# Sheet1.net
KiCad netlist of a schematic drawn in Altium Designer
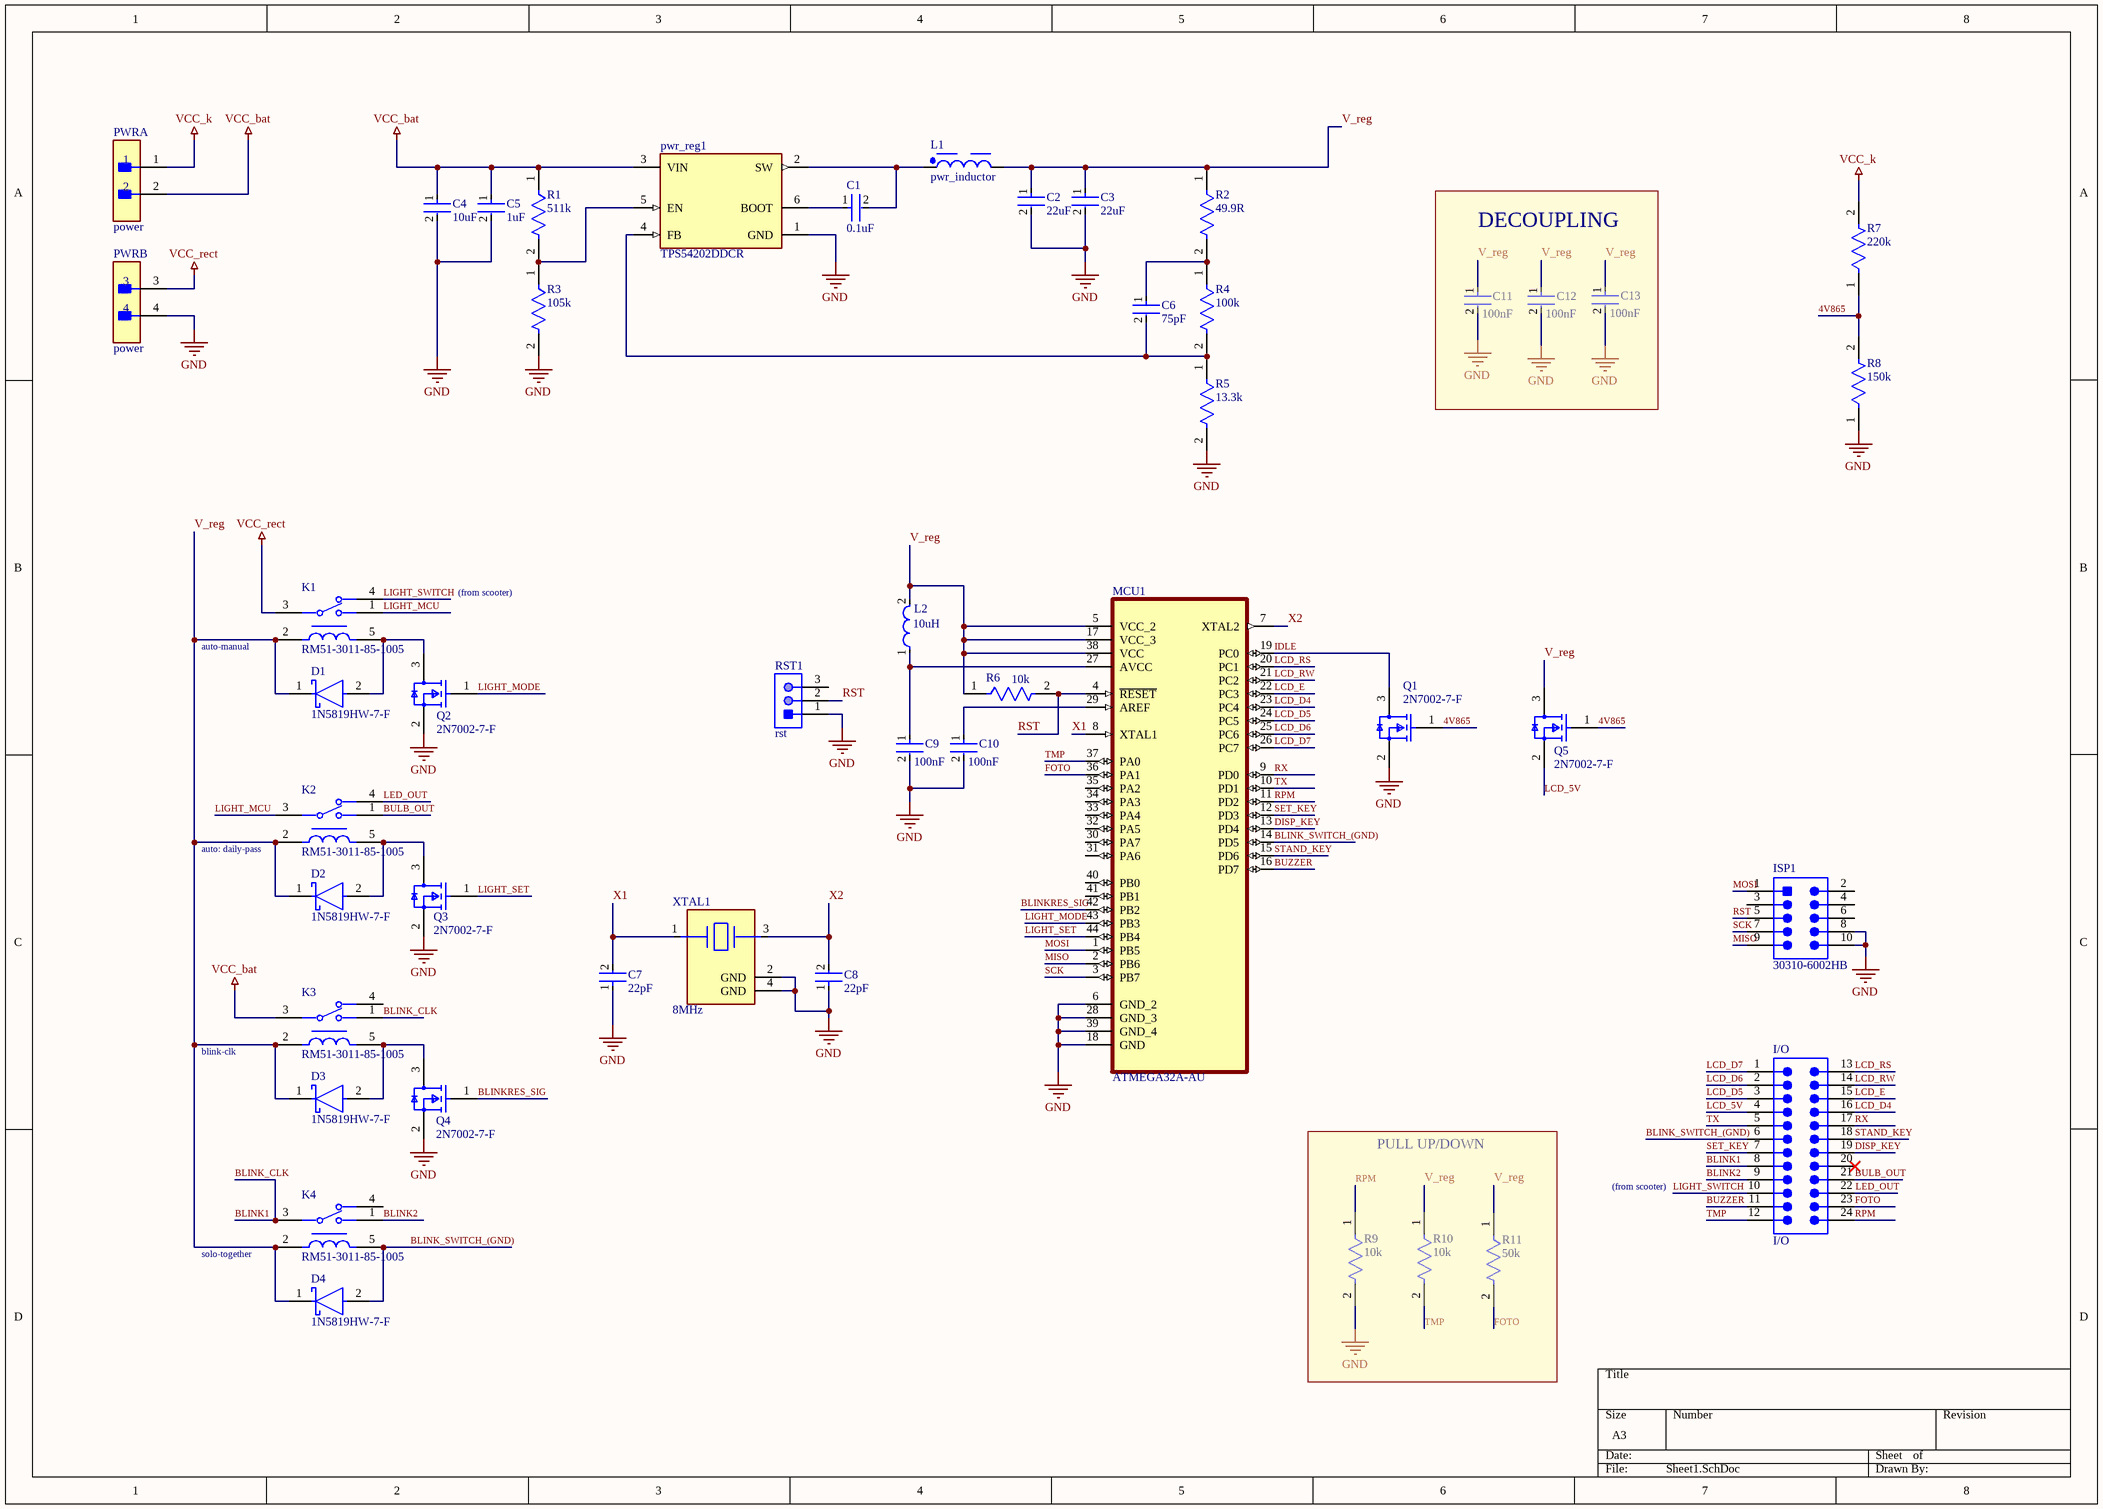
[diagram p0: Sheet1.SchDoc]

(export (version "E")
  (design (tool "Eeschema 10.0.6"))
  (components
    (comp (ref "C1")
      (value "0.1uF")
      (footprint "FP-CL10-IPC_A")
      (description "Cap Ceramic 0.1uF 25V SMD 0603")
      (fields (field (name "VOLTAGE") "50V") (field (name "TOLERANCE") "10%"))
      (libsource (lib "Altium Content Vault") (part "b4654b650e69147ec39a6b967a45e02"))
    )
    (comp (ref "C2")
      (value "22uF")
      (footprint "FP-CL10-IPC_A")
      (description "Cap Ceramic 22uF 25V X7R LOW ESR SMD 0603")
      (fields (field (name "VOLTAGE") "50V") (field (name "TOLERANCE") "10%"))
      (libsource (lib "Altium Content Vault") (part "b4654b650e69147ec39a6b967a45e02"))
    )
    (comp (ref "C3")
      (value "22uF")
      (footprint "FP-CL10-IPC_A")
      (description "Cap Ceramic 22uF 25V X7R LOW ESR SMD 0603")
      (fields (field (name "VOLTAGE") "50V") (field (name "TOLERANCE") "10%"))
      (libsource (lib "Altium Content Vault") (part "b4654b650e69147ec39a6b967a45e02"))
    )
    (comp (ref "C4")
      (value "10uF")
      (footprint "FP-CL10-IPC_A")
      (description "Cap Ceramic 10uF 25V SMD 0603")
      (fields (field (name "VOLTAGE") "50V") (field (name "TOLERANCE") "10%"))
      (libsource (lib "Altium Content Vault") (part "b4654b650e69147ec39a6b967a45e02"))
    )
    (comp (ref "C5")
      (value "1uF")
      (footprint "FP-CL10-IPC_A")
      (description "Cap Ceramic 1uF 25V SMD 0603")
      (fields (field (name "VOLTAGE") "50V") (field (name "TOLERANCE") "10%"))
      (libsource (lib "Altium Content Vault") (part "b4654b650e69147ec39a6b967a45e02"))
    )
    (comp (ref "C6")
      (value "75pF")
      (footprint "FP-CL10-IPC_A")
      (description "Cap Ceramic 75pF 25V SMD 0603")
      (fields (field (name "VOLTAGE") "50V") (field (name "TOLERANCE") "10%"))
      (libsource (lib "Altium Content Vault") (part "b4654b650e69147ec39a6b967a45e02"))
    )
    (comp (ref "C7")
      (value "22pF")
      (footprint "FP-CL10-IPC_A")
      (description "Cap Ceramic 22pF 25V SMD 0603")
      (fields (field (name "VOLTAGE") "50V") (field (name "TOLERANCE") "10%"))
      (libsource (lib "Altium Content Vault") (part "b4654b650e69147ec39a6b967a45e02"))
    )
    (comp (ref "C8")
      (value "22pF")
      (footprint "FP-CL10-IPC_A")
      (description "Cap Ceramic 22pF 25V SMD 0603")
      (fields (field (name "VOLTAGE") "50V") (field (name "TOLERANCE") "10%"))
      (libsource (lib "Altium Content Vault") (part "b4654b650e69147ec39a6b967a45e02"))
    )
    (comp (ref "C9")
      (value "100nF")
      (footprint "FP-CL10-IPC_A")
      (description "Cap Ceramic 100nF 50V X7R ±10% Pad SMD 0603 +125°C T/R")
      (fields (field (name "VOLTAGE") "50V") (field (name "TOLERANCE") "10%"))
      (libsource (lib "Altium Content Vault") (part "b4654b650e69147ec39a6b967a45e02"))
    )
    (comp (ref "C10")
      (value "100nF")
      (footprint "FP-CL10-IPC_A")
      (description "Cap Ceramic 100nF 50V X7R ±10% Pad SMD 0603 +125°C T/R")
      (fields (field (name "VOLTAGE") "50V") (field (name "TOLERANCE") "10%"))
      (libsource (lib "Altium Content Vault") (part "b4654b650e69147ec39a6b967a45e02"))
    )
    (comp (ref "C11")
      (value "100nF")
      (footprint "FP-CL10-IPC_A")
      (description "Cap Ceramic 100nF 50V X7R ±10% Pad SMD 0603 +125°C T/R")
      (fields (field (name "VOLTAGE") "50V") (field (name "TOLERANCE") "10%"))
      (libsource (lib "Altium Content Vault") (part "b4654b650e69147ec39a6b967a45e02"))
    )
    (comp (ref "C12")
      (value "100nF")
      (footprint "FP-CL10-IPC_A")
      (description "Cap Ceramic 100nF 50V X7R ±10% Pad SMD 0603 +125°C T/R")
      (fields (field (name "VOLTAGE") "50V") (field (name "TOLERANCE") "10%"))
      (libsource (lib "Altium Content Vault") (part "b4654b650e69147ec39a6b967a45e02"))
    )
    (comp (ref "C13")
      (value "100nF")
      (footprint "FP-CL10-IPC_A")
      (description "Cap Ceramic 100nF 50V X7R ±10% Pad SMD 0603 +125°C T/R")
      (fields (field (name "VOLTAGE") "50V") (field (name "TOLERANCE") "10%"))
      (libsource (lib "Altium Content Vault") (part "b4654b650e69147ec39a6b967a45e02"))
    )
    (comp (ref "D1")
      (value "1N5819HW-7-F")
      (footprint "FP-SOD123-IPC_A")
      (description "DIODE SCHOTTKY 40V 1A SOD123")
      (libsource (lib "Altium Content Vault") (part "1d6ec82d83fb6aee721767c19dac4b9"))
    )
    (comp (ref "D2")
      (value "1N5819HW-7-F")
      (footprint "FP-SOD123-IPC_A")
      (description "DIODE SCHOTTKY 40V 1A SOD123")
      (libsource (lib "Altium Content Vault") (part "1d6ec82d83fb6aee721767c19dac4b9"))
    )
    (comp (ref "D3")
      (value "1N5819HW-7-F")
      (footprint "FP-SOD123-IPC_A")
      (description "DIODE SCHOTTKY 40V 1A SOD123")
      (libsource (lib "Altium Content Vault") (part "1d6ec82d83fb6aee721767c19dac4b9"))
    )
    (comp (ref "D4")
      (value "1N5819HW-7-F")
      (footprint "FP-SOD123-IPC_A")
      (description "DIODE SCHOTTKY 40V 1A SOD123")
      (libsource (lib "Altium Content Vault") (part "1d6ec82d83fb6aee721767c19dac4b9"))
    )
    (comp (ref "I/O")
      (value "I/O")
      (footprint "649024227222")
      (libsource (lib "Altium Content Vault") (part "Header_Male_2R_24P(A)"))
    )
    (comp (ref "ISP1")
      (value "30310-6002HB")
      (footprint "3M-30310-6002HB-10_V")
      (fields (field (name "MANUFACTURER") "3M"))
      (libsource (lib "Altium Content Vault") (part "CN-2P-M-R10"))
    )
    (comp (ref "K1")
      (value "RM51-3011-85-1005")
      (footprint "FP-1-1721150-0-MFG")
      (description "Relpol\r\nRM51-3011-85-1005\r\nRELAY 10A 5V")
      (fields
        (field (name "MANUFACTURER") "TE")
        (field (name "OCTOPART") "https://octopart.com/1-1721150-0-te+connectivity-41294869")
      )
      (libsource (lib "Altium Content Vault") (part "6d7f6cec76f9d90da65a396cf24d809"))
    )
    (comp (ref "K2")
      (value "RM51-3011-85-1005")
      (footprint "FP-1-1721150-0-MFG")
      (description "Relpol\r\nRM51-3011-85-1005\r\nRELAY 10A 5V")
      (fields
        (field (name "MANUFACTURER") "TE")
        (field (name "OCTOPART") "https://octopart.com/1-1721150-0-te+connectivity-41294869")
      )
      (libsource (lib "Altium Content Vault") (part "6d7f6cec76f9d90da65a396cf24d809"))
    )
    (comp (ref "K3")
      (value "RM51-3011-85-1005")
      (footprint "FP-1-1721150-0-MFG")
      (description "Relpol\r\nRM51-3011-85-1005\r\nRELAY 10A 5V")
      (fields
        (field (name "MANUFACTURER") "TE")
        (field (name "OCTOPART") "https://octopart.com/1-1721150-0-te+connectivity-41294869")
      )
      (libsource (lib "Altium Content Vault") (part "6d7f6cec76f9d90da65a396cf24d809"))
    )
    (comp (ref "K4")
      (value "RM51-3011-85-1005")
      (footprint "FP-1-1721150-0-MFG")
      (description "Relpol\r\nRM51-3011-85-1005\r\nRELAY 10A 5V")
      (fields
        (field (name "MANUFACTURER") "TE")
        (field (name "OCTOPART") "https://octopart.com/1-1721150-0-te+connectivity-41294869")
      )
      (libsource (lib "Altium Content Vault") (part "6d7f6cec76f9d90da65a396cf24d809"))
    )
    (comp (ref "L1")
      (value "pwr_inductor")
      (footprint "WE-PD_7345")
      (description "15uF, 2.7A  HPI0630-150")
      (fields (field (name "TOLERANCE") "20%"))
      (libsource (lib "Altium Content Vault") (part "Inductor - 2"))
    )
    (comp (ref "L2")
      (value "10uH")
      (footprint "FP-CBMF1608-IPC_A")
      (description "SMD Inductors 10uH ±10% 0.38A 0.468Ω 0603")
      (fields (field (name "TOLERANCE") "10%"))
      (libsource (lib "Altium Content Vault") (part "725321dda6339637d4d059423bc1c3c"))
    )
    (comp (ref "MCU1")
      (value "ATMEGA32A-AU")
      (footprint "QFP80P1200X1200X120-44N")
      (description "AVR AVRÂ® ATmega Microcontroller IC 8-Bit 16MHz 32KB (16K x 16) FLASH 44-TQFP (10x10)")
      (fields (field (name "MF") "Microchip"))
      (libsource (lib "ATMEGA32A-AU") (part "ATMEGA32A-AU"))
    )
    (comp (ref "PWR")
      (value "power")
      (footprint "FP-1586042-4-MFG")
      (description "CONN HEADER R/A 4POS 4.2MM")
      (libsource (lib "Altium Content Vault") (part "54be066d535c0aa4221644b3767ed93"))
    )
    (comp (ref "pwr_reg1")
      (value "TPS54202DDCR")
      (footprint "FP-DDC0006A-IPC_B")
      (description "IC REG BUCK ADJ 2A TSOT23-6")
      (libsource (lib "Altium Content Vault") (part "35c2d3f1afc239a386b2ba50eead654"))
    )
    (comp (ref "Q1")
      (value "2N7002-7-F")
      (footprint "FP-SOT23-MFG")
      (description "MOSFET N-CH 60V 115MA SOT23-3")
      (fields (field (name "VOLTAGE") "60V"))
      (libsource (lib "Altium Content Vault") (part "3b9c635fedb024a5347a57b145af9cc"))
    )
    (comp (ref "Q2")
      (value "2N7002-7-F")
      (footprint "FP-SOT23-MFG")
      (description "MOSFET N-CH 60V 115MA SOT23-3")
      (fields (field (name "VOLTAGE") "60V"))
      (libsource (lib "Altium Content Vault") (part "3b9c635fedb024a5347a57b145af9cc"))
    )
    (comp (ref "Q3")
      (value "2N7002-7-F")
      (footprint "FP-SOT23-MFG")
      (description "MOSFET N-CH 60V 115MA SOT23-3")
      (fields (field (name "VOLTAGE") "60V"))
      (libsource (lib "Altium Content Vault") (part "3b9c635fedb024a5347a57b145af9cc"))
    )
    (comp (ref "Q4")
      (value "2N7002-7-F")
      (footprint "FP-SOT23-MFG")
      (description "MOSFET N-CH 60V 115MA SOT23-3")
      (fields (field (name "VOLTAGE") "60V"))
      (libsource (lib "Altium Content Vault") (part "3b9c635fedb024a5347a57b145af9cc"))
    )
    (comp (ref "Q5")
      (value "2N7002-7-F")
      (footprint "FP-SOT23-MFG")
      (description "MOSFET N-CH 60V 115MA SOT23-3")
      (fields (field (name "VOLTAGE") "60V"))
      (libsource (lib "Altium Content Vault") (part "3b9c635fedb024a5347a57b145af9cc"))
    )
    (comp (ref "R1")
      (value "511k")
      (footprint "FP-CRCW0603-e3-IPC_A")
      (description "511kΩ, 0.1W, 0603")
      (fields (field (name "TOLERANCE") "1%"))
      (libsource (lib "Altium Content Vault") (part "1029c3af85768c4190bb7ad29bc67b5"))
    )
    (comp (ref "R2")
      (value "49.9R")
      (footprint "FP-CRCW0603-e3-IPC_A")
      (description "49.9Ω, 0.1W, 0603")
      (fields (field (name "TOLERANCE") "1%"))
      (libsource (lib "Altium Content Vault") (part "1029c3af85768c4190bb7ad29bc67b5"))
    )
    (comp (ref "R3")
      (value "105k")
      (footprint "FP-CRCW0603-e3-IPC_A")
      (description "105kΩ, 0.1W, 0603")
      (fields (field (name "TOLERANCE") "1%"))
      (libsource (lib "Altium Content Vault") (part "1029c3af85768c4190bb7ad29bc67b5"))
    )
    (comp (ref "R4")
      (value "100k")
      (footprint "FP-CRCW0603-e3-IPC_A")
      (description "100kΩ, 0.1W, 0603")
      (fields (field (name "TOLERANCE") "1%"))
      (libsource (lib "Altium Content Vault") (part "1029c3af85768c4190bb7ad29bc67b5"))
    )
    (comp (ref "R5")
      (value "13.3k")
      (footprint "FP-CRCW0603-e3-IPC_A")
      (description "13.3kΩ, 0.1W, 0603")
      (fields (field (name "TOLERANCE") "1%"))
      (libsource (lib "Altium Content Vault") (part "1029c3af85768c4190bb7ad29bc67b5"))
    )
    (comp (ref "R6")
      (value "10k")
      (footprint "FP-CRCW0603-e3-IPC_A")
      (description "10kΩ, 0.1W, 0603")
      (fields (field (name "TOLERANCE") "1%"))
      (libsource (lib "Altium Content Vault") (part "1029c3af85768c4190bb7ad29bc67b5"))
    )
    (comp (ref "R7")
      (value "220k")
      (footprint "FP-CRCW0603-e3-IPC_A")
      (description "220kΩ, 0.1W, 0603")
      (fields (field (name "TOLERANCE") "1%"))
      (libsource (lib "Altium Content Vault") (part "1029c3af85768c4190bb7ad29bc67b5"))
    )
    (comp (ref "R8")
      (value "150k")
      (footprint "FP-CRCW0603-e3-IPC_A")
      (description "150kΩ, 0.1W, 0603")
      (fields (field (name "TOLERANCE") "1%"))
      (libsource (lib "Altium Content Vault") (part "1029c3af85768c4190bb7ad29bc67b5"))
    )
    (comp (ref "R9")
      (value "10k")
      (footprint "FP-CRCW0603-e3-IPC_A")
      (description "10kΩ, 0.1W, 0603")
      (fields (field (name "TOLERANCE") "1%"))
      (libsource (lib "Altium Content Vault") (part "1029c3af85768c4190bb7ad29bc67b5"))
    )
    (comp (ref "R10")
      (value "10k")
      (footprint "FP-CRCW0603-e3-IPC_A")
      (description "10kΩ, 0.1W, 0603")
      (fields (field (name "TOLERANCE") "1%"))
      (libsource (lib "Altium Content Vault") (part "1029c3af85768c4190bb7ad29bc67b5"))
    )
    (comp (ref "R11")
      (value "50k")
      (footprint "FP-CRCW0603-e3-IPC_A")
      (description "50kΩ, 0.1W, 0603")
      (fields (field (name "TOLERANCE") "1%"))
      (libsource (lib "Altium Content Vault") (part "1029c3af85768c4190bb7ad29bc67b5"))
    )
    (comp (ref "RST1")
      (value "rst")
      (footprint "MOLX-22-28-4033_V")
      (description "Male Header, Pitch 2.54 mm, 1 x 3 Position, Height 8.38 mm, Tail Length 3.18 mm, RoHS, Bulk")
      (fields (field (name "MANUFACTURER") "Molex"))
      (libsource (lib "Altium Content Vault") (part "CN-1P-M-R3"))
    )
    (comp (ref "XTAL1")
      (value "8MHz")
      (footprint "FP-LFXTAL055663REEL-MFG")
      (description "LFXTAL055663REEL\r\nCRYSTAL 8.0000MHZ 18PF SMD")
      (libsource (lib "Altium Content Vault") (part "b89083c918a6a788f8f4b4140568890"))
    )
  )
  (nets
    (net (code "1") (name "/4V865") (class "Default")
      (node (ref "Q1") (pin "1") (pinfunction "G_1") (pintype "passive"))
      (node (ref "Q5") (pin "1") (pinfunction "G_1") (pintype "passive"))
      (node (ref "R7") (pin "1") (pinfunction "1_1") (pintype "passive"))
      (node (ref "R8") (pin "2") (pinfunction "2_2") (pintype "passive"))
    )
    (net (code "3") (name "/BLINK1") (class "Default")
      (node (ref "I/O") (pin "8") (pinfunction "8_8") (pintype "passive"))
      (node (ref "K3") (pin "1") (pinfunction "1_1") (pintype "passive"))
      (node (ref "K4") (pin "3") (pinfunction "3_3") (pintype "passive"))
    )
    (net (code "4") (name "/BLINK2") (class "Default")
      (node (ref "I/O") (pin "9") (pinfunction "9_9") (pintype "passive"))
      (node (ref "K4") (pin "1") (pinfunction "1_1") (pintype "passive"))
    )
    (net (code "5") (name "/BLINKRES_SIG") (class "Default")
      (node (ref "MCU1") (pin "42") (pinfunction "PB2_42") (pintype "bidirectional"))
      (node (ref "Q4") (pin "1") (pinfunction "G_1") (pintype "passive"))
    )
    (net (code "6") (name "/BLINK_SWITCH_(GND)") (class "Default")
      (node (ref "D4") (pin "2") (pinfunction "A_2") (pintype "passive"))
      (node (ref "I/O") (pin "6") (pinfunction "6_6") (pintype "passive"))
      (node (ref "K4") (pin "5") (pinfunction "5_5") (pintype "passive"))
      (node (ref "MCU1") (pin "14") (pinfunction "PD5_14") (pintype "bidirectional"))
    )
    (net (code "7") (name "/BULB_OUT") (class "Default")
      (node (ref "I/O") (pin "21") (pinfunction "21_21") (pintype "passive"))
      (node (ref "K2") (pin "1") (pinfunction "1_1") (pintype "passive"))
    )
    (net (code "8") (name "/BUZZER") (class "Default")
      (node (ref "I/O") (pin "11") (pinfunction "11_11") (pintype "passive"))
      (node (ref "MCU1") (pin "16") (pinfunction "PD7_16") (pintype "bidirectional"))
    )
    (net (code "9") (name "/DISP_KEY") (class "Default")
      (node (ref "I/O") (pin "19") (pinfunction "19_19") (pintype "passive"))
      (node (ref "MCU1") (pin "13") (pinfunction "PD4_13") (pintype "bidirectional"))
    )
    (net (code "10") (name "/FOTO") (class "Default")
      (node (ref "I/O") (pin "23") (pinfunction "23_23") (pintype "passive"))
      (node (ref "MCU1") (pin "36") (pinfunction "PA1_36") (pintype "bidirectional"))
      (node (ref "R11") (pin "2") (pinfunction "2_2") (pintype "passive"))
    )
    (net (code "11") (name "/IDLE") (class "Default")
      (node (ref "MCU1") (pin "19") (pinfunction "PC0_19") (pintype "bidirectional"))
      (node (ref "Q1") (pin "3") (pinfunction "D_3") (pintype "passive"))
    )
    (net (code "12") (name "/LCD_5V") (class "Default")
      (node (ref "I/O") (pin "4") (pinfunction "4_4") (pintype "passive"))
      (node (ref "Q5") (pin "2") (pinfunction "S_2") (pintype "passive"))
    )
    (net (code "13") (name "/LCD_D4") (class "Default")
      (node (ref "I/O") (pin "16") (pinfunction "16_16") (pintype "passive"))
      (node (ref "MCU1") (pin "23") (pinfunction "PC4_23") (pintype "bidirectional"))
    )
    (net (code "14") (name "/LCD_D5") (class "Default")
      (node (ref "I/O") (pin "3") (pinfunction "3_3") (pintype "passive"))
      (node (ref "MCU1") (pin "24") (pinfunction "PC5_24") (pintype "bidirectional"))
    )
    (net (code "15") (name "/LCD_D6") (class "Default")
      (node (ref "I/O") (pin "2") (pinfunction "2_2") (pintype "passive"))
      (node (ref "MCU1") (pin "25") (pinfunction "PC6_25") (pintype "bidirectional"))
    )
    (net (code "16") (name "/LCD_D7") (class "Default")
      (node (ref "I/O") (pin "1") (pinfunction "1_1") (pintype "passive"))
      (node (ref "MCU1") (pin "26") (pinfunction "PC7_26") (pintype "bidirectional"))
    )
    (net (code "17") (name "/LCD_E") (class "Default")
      (node (ref "I/O") (pin "15") (pinfunction "15_15") (pintype "passive"))
      (node (ref "MCU1") (pin "22") (pinfunction "PC3_22") (pintype "bidirectional"))
    )
    (net (code "18") (name "/LCD_RS") (class "Default")
      (node (ref "I/O") (pin "13") (pinfunction "13_13") (pintype "passive"))
      (node (ref "MCU1") (pin "20") (pinfunction "PC1_20") (pintype "bidirectional"))
    )
    (net (code "19") (name "/LCD_RW") (class "Default")
      (node (ref "I/O") (pin "14") (pinfunction "14_14") (pintype "passive"))
      (node (ref "MCU1") (pin "21") (pinfunction "PC2_21") (pintype "bidirectional"))
    )
    (net (code "20") (name "/LED_OUT") (class "Default")
      (node (ref "I/O") (pin "22") (pinfunction "22_22") (pintype "passive"))
      (node (ref "K2") (pin "4") (pinfunction "4_4") (pintype "passive"))
    )
    (net (code "21") (name "/LIGHT_MCU") (class "Default")
      (node (ref "K1") (pin "1") (pinfunction "1_1") (pintype "passive"))
      (node (ref "K2") (pin "3") (pinfunction "3_3") (pintype "passive"))
    )
    (net (code "22") (name "/LIGHT_MODE") (class "Default")
      (node (ref "MCU1") (pin "43") (pinfunction "PB3_43") (pintype "bidirectional"))
      (node (ref "Q2") (pin "1") (pinfunction "G_1") (pintype "passive"))
    )
    (net (code "23") (name "/LIGHT_SET") (class "Default")
      (node (ref "MCU1") (pin "44") (pinfunction "PB4_44") (pintype "bidirectional"))
      (node (ref "Q3") (pin "1") (pinfunction "G_1") (pintype "passive"))
    )
    (net (code "24") (name "/LIGHT_SWITCH") (class "Default")
      (node (ref "I/O") (pin "10") (pinfunction "10_10") (pintype "passive"))
      (node (ref "K1") (pin "4") (pinfunction "4_4") (pintype "passive"))
    )
    (net (code "25") (name "/MISO") (class "Default")
      (node (ref "ISP1") (pin "9") (pinfunction "9_9") (pintype "passive"))
      (node (ref "MCU1") (pin "2") (pinfunction "PB6_2") (pintype "bidirectional"))
    )
    (net (code "26") (name "/MOSI") (class "Default")
      (node (ref "ISP1") (pin "1") (pinfunction "1_1") (pintype "passive"))
      (node (ref "MCU1") (pin "1") (pinfunction "PB5_1") (pintype "bidirectional"))
    )
    (net (code "27") (name "/RPM") (class "Default")
      (node (ref "I/O") (pin "24") (pinfunction "24_24") (pintype "passive"))
      (node (ref "MCU1") (pin "11") (pinfunction "PD2_11") (pintype "bidirectional"))
      (node (ref "R9") (pin "1") (pinfunction "1_1") (pintype "passive"))
    )
    (net (code "28") (name "/RST") (class "Default")
      (node (ref "ISP1") (pin "5") (pinfunction "5_5") (pintype "passive"))
      (node (ref "MCU1") (pin "4") (pinfunction "~{RESET}_4") (pintype "input"))
      (node (ref "R6") (pin "2") (pinfunction "2_2") (pintype "passive"))
      (node (ref "RST1") (pin "2") (pinfunction "2_2") (pintype "passive"))
    )
    (net (code "29") (name "/RX") (class "Default")
      (node (ref "I/O") (pin "17") (pinfunction "17_17") (pintype "passive"))
      (node (ref "MCU1") (pin "9") (pinfunction "PD0_9") (pintype "bidirectional"))
    )
    (net (code "30") (name "/SCK") (class "Default")
      (node (ref "ISP1") (pin "7") (pinfunction "7_7") (pintype "passive"))
      (node (ref "MCU1") (pin "3") (pinfunction "PB7_3") (pintype "bidirectional"))
    )
    (net (code "31") (name "/SET_KEY") (class "Default")
      (node (ref "I/O") (pin "7") (pinfunction "7_7") (pintype "passive"))
      (node (ref "MCU1") (pin "12") (pinfunction "PD3_12") (pintype "bidirectional"))
    )
    (net (code "32") (name "/STAND_KEY") (class "Default")
      (node (ref "I/O") (pin "18") (pinfunction "18_18") (pintype "passive"))
      (node (ref "MCU1") (pin "15") (pinfunction "PD6_15") (pintype "bidirectional"))
    )
    (net (code "33") (name "/TMP") (class "Default")
      (node (ref "I/O") (pin "12") (pinfunction "12_12") (pintype "passive"))
      (node (ref "MCU1") (pin "37") (pinfunction "PA0_37") (pintype "bidirectional"))
      (node (ref "R10") (pin "2") (pinfunction "2_2") (pintype "passive"))
    )
    (net (code "34") (name "/TX") (class "Default")
      (node (ref "I/O") (pin "5") (pinfunction "5_5") (pintype "passive"))
      (node (ref "MCU1") (pin "10") (pinfunction "PD1_10") (pintype "bidirectional"))
    )
    (net (code "35") (name "/V_reg") (class "Default")
      (node (ref "C11") (pin "1") (pinfunction "1_1") (pintype "passive"))
      (node (ref "C12") (pin "1") (pinfunction "1_1") (pintype "passive"))
      (node (ref "C13") (pin "1") (pinfunction "1_1") (pintype "passive"))
      (node (ref "C2") (pin "1") (pinfunction "1_1") (pintype "passive"))
      (node (ref "C3") (pin "1") (pinfunction "1_1") (pintype "passive"))
      (node (ref "D1") (pin "1") (pinfunction "C_1") (pintype "passive"))
      (node (ref "D2") (pin "1") (pinfunction "C_1") (pintype "passive"))
      (node (ref "D3") (pin "1") (pinfunction "C_1") (pintype "passive"))
      (node (ref "D4") (pin "1") (pinfunction "C_1") (pintype "passive"))
      (node (ref "K1") (pin "2") (pinfunction "2_2") (pintype "passive"))
      (node (ref "K2") (pin "2") (pinfunction "2_2") (pintype "passive"))
      (node (ref "K3") (pin "2") (pinfunction "2_2") (pintype "passive"))
      (node (ref "K4") (pin "2") (pinfunction "2_2") (pintype "passive"))
      (node (ref "L1") (pin "2") (pinfunction "2_2") (pintype "passive"))
      (node (ref "L2") (pin "2") (pinfunction "2_2") (pintype "passive"))
      (node (ref "MCU1") (pin "17") (pinfunction "VCC_3_17") (pintype "power_in"))
      (node (ref "MCU1") (pin "38") (pinfunction "VCC_38") (pintype "power_in"))
      (node (ref "MCU1") (pin "5") (pinfunction "VCC_2_5") (pintype "power_in"))
      (node (ref "Q5") (pin "3") (pinfunction "D_3") (pintype "passive"))
      (node (ref "R10") (pin "1") (pinfunction "1_1") (pintype "passive"))
      (node (ref "R11") (pin "1") (pinfunction "1_1") (pintype "passive"))
      (node (ref "R2") (pin "1") (pinfunction "1_1") (pintype "passive"))
      (node (ref "R6") (pin "1") (pinfunction "1_1") (pintype "passive"))
    )
    (net (code "36") (name "/X1") (class "Default")
      (node (ref "C7") (pin "2") (pinfunction "2_2") (pintype "passive"))
      (node (ref "MCU1") (pin "8") (pinfunction "XTAL1_8") (pintype "input"))
      (node (ref "XTAL1") (pin "1") (pinfunction "1_CRYSTAL_1") (pintype "passive"))
    )
    (net (code "37") (name "/X2") (class "Default")
      (node (ref "C8") (pin "2") (pinfunction "2_2") (pintype "passive"))
      (node (ref "MCU1") (pin "7") (pinfunction "XTAL2_7") (pintype "output"))
      (node (ref "XTAL1") (pin "3") (pinfunction "2_CRYSTAL_3") (pintype "passive"))
    )
    (net (code "38") (name "GND") (class "Default")
      (node (ref "C10") (pin "2") (pinfunction "2_2") (pintype "passive"))
      (node (ref "C11") (pin "2") (pinfunction "2_2") (pintype "passive"))
      (node (ref "C12") (pin "2") (pinfunction "2_2") (pintype "passive"))
      (node (ref "C13") (pin "2") (pinfunction "2_2") (pintype "passive"))
      (node (ref "C2") (pin "2") (pinfunction "2_2") (pintype "passive"))
      (node (ref "C3") (pin "2") (pinfunction "2_2") (pintype "passive"))
      (node (ref "C4") (pin "2") (pinfunction "2_2") (pintype "passive"))
      (node (ref "C5") (pin "2") (pinfunction "2_2") (pintype "passive"))
      (node (ref "C7") (pin "1") (pinfunction "1_1") (pintype "passive"))
      (node (ref "C8") (pin "1") (pinfunction "1_1") (pintype "passive"))
      (node (ref "C9") (pin "2") (pinfunction "2_2") (pintype "passive"))
      (node (ref "ISP1") (pin "10") (pinfunction "10_10") (pintype "passive"))
      (node (ref "ISP1") (pin "8") (pinfunction "8_8") (pintype "passive"))
      (node (ref "MCU1") (pin "18") (pinfunction "GND_18") (pintype "passive"))
      (node (ref "MCU1") (pin "28") (pinfunction "GND_3_28") (pintype "passive"))
      (node (ref "MCU1") (pin "39") (pinfunction "GND_4_39") (pintype "passive"))
      (node (ref "MCU1") (pin "6") (pinfunction "GND_2_6") (pintype "passive"))
      (node (ref "PWR") (pin "4") (pinfunction "4_4") (pintype "passive"))
      (node (ref "Q1") (pin "2") (pinfunction "S_2") (pintype "passive"))
      (node (ref "Q2") (pin "2") (pinfunction "S_2") (pintype "passive"))
      (node (ref "Q3") (pin "2") (pinfunction "S_2") (pintype "passive"))
      (node (ref "Q4") (pin "2") (pinfunction "S_2") (pintype "passive"))
      (node (ref "R3") (pin "2") (pinfunction "2_2") (pintype "passive"))
      (node (ref "R5") (pin "2") (pinfunction "2_2") (pintype "passive"))
      (node (ref "R8") (pin "1") (pinfunction "1_1") (pintype "passive"))
      (node (ref "R9") (pin "2") (pinfunction "2_2") (pintype "passive"))
      (node (ref "RST1") (pin "1") (pinfunction "1_1") (pintype "passive"))
      (node (ref "XTAL1") (pin "2") (pinfunction "GND_2") (pintype "power_in"))
      (node (ref "XTAL1") (pin "4") (pinfunction "GND_4") (pintype "power_in"))
      (node (ref "pwr_reg1") (pin "1") (pinfunction "GND_1") (pintype "power_in"))
    )
    (net (code "39") (name "Net-(C6-Pad1)") (class "Default")
      (node (ref "C6") (pin "1") (pinfunction "1_1") (pintype "passive"))
      (node (ref "R2") (pin "2") (pinfunction "2_2") (pintype "passive"))
      (node (ref "R4") (pin "1") (pinfunction "1_1") (pintype "passive"))
    )
    (net (code "40") (name "Net-(D1-A)") (class "Default")
      (node (ref "D1") (pin "2") (pinfunction "A_2") (pintype "passive"))
      (node (ref "K1") (pin "5") (pinfunction "5_5") (pintype "passive"))
      (node (ref "Q2") (pin "3") (pinfunction "D_3") (pintype "passive"))
    )
    (net (code "41") (name "Net-(D2-A)") (class "Default")
      (node (ref "D2") (pin "2") (pinfunction "A_2") (pintype "passive"))
      (node (ref "K2") (pin "5") (pinfunction "5_5") (pintype "passive"))
      (node (ref "Q3") (pin "3") (pinfunction "D_3") (pintype "passive"))
    )
    (net (code "42") (name "Net-(D3-A)") (class "Default")
      (node (ref "D3") (pin "2") (pinfunction "A_2") (pintype "passive"))
      (node (ref "K3") (pin "5") (pinfunction "5_5") (pintype "passive"))
      (node (ref "Q4") (pin "3") (pinfunction "D_3") (pintype "passive"))
    )
    (net (code "43") (name "Net-(MCU1-AREF)") (class "Default")
      (node (ref "C10") (pin "1") (pinfunction "1_1") (pintype "passive"))
      (node (ref "MCU1") (pin "29") (pinfunction "AREF_29") (pintype "input"))
    )
    (net (code "44") (name "Net-(MCU1-AVCC)") (class "Default")
      (node (ref "C9") (pin "1") (pinfunction "1_1") (pintype "passive"))
      (node (ref "L2") (pin "1") (pinfunction "1_1") (pintype "passive"))
      (node (ref "MCU1") (pin "27") (pinfunction "AVCC_27") (pintype "power_in"))
    )
    (net (code "45") (name "Net-(pwr_reg1-BOOT)") (class "Default")
      (node (ref "C1") (pin "1") (pinfunction "1_1") (pintype "passive"))
      (node (ref "pwr_reg1") (pin "6") (pinfunction "BOOT_6") (pintype "passive"))
    )
    (net (code "46") (name "Net-(pwr_reg1-EN)") (class "Default")
      (node (ref "R1") (pin "2") (pinfunction "2_2") (pintype "passive"))
      (node (ref "R3") (pin "1") (pinfunction "1_1") (pintype "passive"))
      (node (ref "pwr_reg1") (pin "5") (pinfunction "EN_5") (pintype "input"))
    )
    (net (code "47") (name "Net-(pwr_reg1-FB)") (class "Default")
      (node (ref "C6") (pin "2") (pinfunction "2_2") (pintype "passive"))
      (node (ref "R4") (pin "2") (pinfunction "2_2") (pintype "passive"))
      (node (ref "R5") (pin "1") (pinfunction "1_1") (pintype "passive"))
      (node (ref "pwr_reg1") (pin "4") (pinfunction "FB_4") (pintype "input"))
    )
    (net (code "48") (name "Net-(pwr_reg1-SW)") (class "Default")
      (node (ref "C1") (pin "2") (pinfunction "2_2") (pintype "passive"))
      (node (ref "L1") (pin "1") (pinfunction "1_1") (pintype "passive"))
      (node (ref "pwr_reg1") (pin "2") (pinfunction "SW_2") (pintype "output"))
    )
    (net (code "49") (name "VCC_bat") (class "Default")
      (node (ref "C4") (pin "1") (pinfunction "1_1") (pintype "passive"))
      (node (ref "C5") (pin "1") (pinfunction "1_1") (pintype "passive"))
      (node (ref "K3") (pin "3") (pinfunction "3_3") (pintype "passive"))
      (node (ref "PWR") (pin "2") (pinfunction "2_2") (pintype "passive"))
      (node (ref "R1") (pin "1") (pinfunction "1_1") (pintype "passive"))
      (node (ref "pwr_reg1") (pin "3") (pinfunction "VIN_3") (pintype "power_in"))
    )
    (net (code "50") (name "VCC_k") (class "Default")
      (node (ref "PWR") (pin "1") (pinfunction "1_1") (pintype "passive"))
      (node (ref "R7") (pin "2") (pinfunction "2_2") (pintype "passive"))
    )
    (net (code "51") (name "VCC_rect") (class "Default")
      (node (ref "K1") (pin "3") (pinfunction "3_3") (pintype "passive"))
      (node (ref "PWR") (pin "3") (pinfunction "3_3") (pintype "passive"))
    )
    (net (code "52") (name "unconnected-(I/O-Pad20)") (class "Default")
      (node (ref "I/O") (pin "20") (pinfunction "20_20") (pintype "passive+no_connect"))
    )
    (net (code "53") (name "unconnected-(ISP1-Pad2)") (class "Default")
      (node (ref "ISP1") (pin "2") (pinfunction "2_2") (pintype "passive"))
    )
    (net (code "54") (name "unconnected-(ISP1-Pad3)") (class "Default")
      (node (ref "ISP1") (pin "3") (pinfunction "3_3") (pintype "passive"))
    )
    (net (code "55") (name "unconnected-(ISP1-Pad4)") (class "Default")
      (node (ref "ISP1") (pin "4") (pinfunction "4_4") (pintype "passive"))
    )
    (net (code "56") (name "unconnected-(ISP1-Pad6)") (class "Default")
      (node (ref "ISP1") (pin "6") (pinfunction "6_6") (pintype "passive"))
    )
    (net (code "57") (name "unconnected-(K3-Pad4)") (class "Default")
      (node (ref "K3") (pin "4") (pinfunction "4_4") (pintype "passive"))
    )
    (net (code "58") (name "unconnected-(K4-Pad4)") (class "Default")
      (node (ref "K4") (pin "4") (pinfunction "4_4") (pintype "passive"))
    )
    (net (code "59") (name "unconnected-(MCU1-PA2-Pad35)") (class "Default")
      (node (ref "MCU1") (pin "35") (pinfunction "PA2_35") (pintype "bidirectional"))
    )
    (net (code "60") (name "unconnected-(MCU1-PA3-Pad34)") (class "Default")
      (node (ref "MCU1") (pin "34") (pinfunction "PA3_34") (pintype "bidirectional"))
    )
    (net (code "61") (name "unconnected-(MCU1-PA4-Pad33)") (class "Default")
      (node (ref "MCU1") (pin "33") (pinfunction "PA4_33") (pintype "bidirectional"))
    )
    (net (code "62") (name "unconnected-(MCU1-PA5-Pad32)") (class "Default")
      (node (ref "MCU1") (pin "32") (pinfunction "PA5_32") (pintype "bidirectional"))
    )
    (net (code "63") (name "unconnected-(MCU1-PA6-Pad31)") (class "Default")
      (node (ref "MCU1") (pin "31") (pinfunction "PA6_31") (pintype "bidirectional"))
    )
    (net (code "64") (name "unconnected-(MCU1-PA7-Pad30)") (class "Default")
      (node (ref "MCU1") (pin "30") (pinfunction "PA7_30") (pintype "bidirectional"))
    )
    (net (code "65") (name "unconnected-(MCU1-PB0-Pad40)") (class "Default")
      (node (ref "MCU1") (pin "40") (pinfunction "PB0_40") (pintype "bidirectional"))
    )
    (net (code "66") (name "unconnected-(MCU1-PB1-Pad41)") (class "Default")
      (node (ref "MCU1") (pin "41") (pinfunction "PB1_41") (pintype "bidirectional"))
    )
    (net (code "67") (name "unconnected-(RST1-Pad3)") (class "Default")
      (node (ref "RST1") (pin "3") (pinfunction "3_3") (pintype "passive"))
    )
  )
)
